# full_Bridge_v2.net
KiCad netlist of a schematic drawn in EAGLE
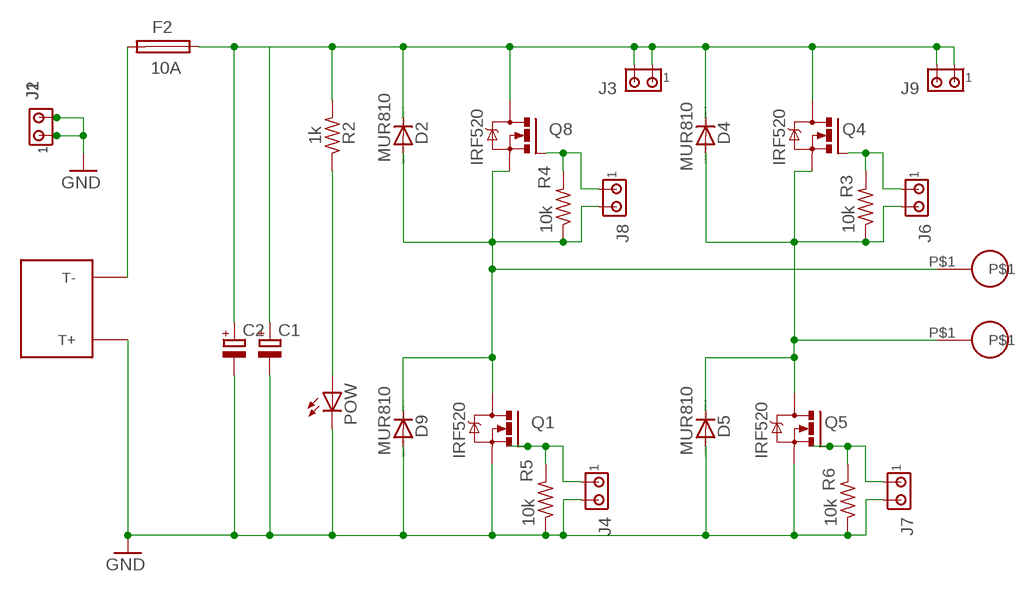
[diagram p0: schematic, sheet 1]

(export (version "E")
  (design (tool "Eeschema 10.0.6"))
  (components
    (comp (ref "AC1")
      (value "TERMINAL")
      (footprint "eagle-import:TERMINAL")
      (libsource (lib "eagle-import") (part "TERMINAL"))
    )
    (comp (ref "AC2")
      (value "TERMINAL")
      (footprint "eagle-import:TERMINAL")
      (libsource (lib "eagle-import") (part "TERMINAL"))
    )
    (comp (ref "C1")
      (value "CPOL-EUTT5D10")
      (footprint "eagle-import:TT5D10")
      (libsource (lib "eagle-import") (part "CPOL-EUTT5D10"))
    )
    (comp (ref "C2")
      (value "CPOL-EUTT5D10")
      (footprint "eagle-import:TT5D10")
      (libsource (lib "eagle-import") (part "CPOL-EUTT5D10"))
    )
    (comp (ref "D2")
      (value "MUR810")
      (footprint "eagle-import:TO220ACS")
      (libsource (lib "eagle-import") (part "MUR810"))
    )
    (comp (ref "D4")
      (value "MUR810")
      (footprint "eagle-import:TO220ACS")
      (libsource (lib "eagle-import") (part "MUR810"))
    )
    (comp (ref "D5")
      (value "MUR810")
      (footprint "eagle-import:TO220ACS")
      (libsource (lib "eagle-import") (part "MUR810"))
    )
    (comp (ref "D9")
      (value "MUR810")
      (footprint "eagle-import:TO220ACS")
      (libsource (lib "eagle-import") (part "MUR810"))
    )
    (comp (ref "F2")
      (value "10A")
      (footprint "eagle-import:SH22,5A")
      (fields (field (name "MPN") "0031.7701.11"))
      (libsource (lib "eagle-import") (part "SH22,5A"))
    )
    (comp (ref "J1")
      (value "MTA02-100")
      (footprint "eagle-import:10X02MTA")
      (libsource (lib "eagle-import") (part "MTA02-100"))
    )
    (comp (ref "J2")
      (value "MTA02-100")
      (footprint "eagle-import:10X02MTA")
      (libsource (lib "eagle-import") (part "MTA02-100"))
    )
    (comp (ref "J3")
      (value "MTA02-100")
      (footprint "eagle-import:10X02MTA")
      (libsource (lib "eagle-import") (part "MTA02-100"))
    )
    (comp (ref "J4")
      (value "MTA02-100")
      (footprint "eagle-import:10X02MTA")
      (libsource (lib "eagle-import") (part "MTA02-100"))
    )
    (comp (ref "J6")
      (value "MTA02-100")
      (footprint "eagle-import:10X02MTA")
      (libsource (lib "eagle-import") (part "MTA02-100"))
    )
    (comp (ref "J7")
      (value "MTA02-100")
      (footprint "eagle-import:10X02MTA")
      (libsource (lib "eagle-import") (part "MTA02-100"))
    )
    (comp (ref "J8")
      (value "MTA02-100")
      (footprint "eagle-import:10X02MTA")
      (libsource (lib "eagle-import") (part "MTA02-100"))
    )
    (comp (ref "J9")
      (value "MTA02-100")
      (footprint "eagle-import:10X02MTA")
      (libsource (lib "eagle-import") (part "MTA02-100"))
    )
    (comp (ref "POW")
      (value "LED3MM")
      (footprint "eagle-import:LED3MM")
      (libsource (lib "eagle-import") (part "LED3MM"))
    )
    (comp (ref "Q1")
      (value "IRF520")
      (footprint "eagle-import:TO220BV")
      (libsource (lib "eagle-import") (part "IRF520"))
    )
    (comp (ref "Q4")
      (value "IRF520")
      (footprint "eagle-import:TO220BV")
      (libsource (lib "eagle-import") (part "IRF520"))
    )
    (comp (ref "Q5")
      (value "IRF520")
      (footprint "eagle-import:TO220BV")
      (libsource (lib "eagle-import") (part "IRF520"))
    )
    (comp (ref "Q8")
      (value "IRF520")
      (footprint "eagle-import:TO220BV")
      (libsource (lib "eagle-import") (part "IRF520"))
    )
    (comp (ref "R2")
      (value "1k")
      (footprint "eagle-import:0207_12")
      (libsource (lib "eagle-import") (part "R-US_0207/12"))
    )
    (comp (ref "R3")
      (value "10k")
      (footprint "eagle-import:0204_7")
      (libsource (lib "eagle-import") (part "R-US_0204/7"))
    )
    (comp (ref "R4")
      (value "10k")
      (footprint "eagle-import:0204_7")
      (libsource (lib "eagle-import") (part "R-US_0204/7"))
    )
    (comp (ref "R5")
      (value "10k")
      (footprint "eagle-import:0204_7")
      (libsource (lib "eagle-import") (part "R-US_0204/7"))
    )
    (comp (ref "R6")
      (value "10k")
      (footprint "eagle-import:0204_7")
      (libsource (lib "eagle-import") (part "R-US_0204/7"))
    )
    (comp (ref "U$5")
      (value "CONNECTOR_BIG")
      (footprint "eagle-import:CONNECTOR_BIG")
      (libsource (lib "eagle-import") (part "CONNECTOR_BIG"))
    )
  )
  (nets
    (net (code "1") (name "GND") (class "Default")
      (node (ref "C1") (pin "-") (pinfunction "-_-") (pintype "passive"))
      (node (ref "C2") (pin "-") (pinfunction "-_-") (pintype "passive"))
      (node (ref "D5") (pin "A") (pinfunction "A_A") (pintype "passive"))
      (node (ref "D9") (pin "A") (pinfunction "A_A") (pintype "passive"))
      (node (ref "J1") (pin "1") (pinfunction "1_1") (pintype "passive"))
      (node (ref "J1") (pin "2") (pinfunction "2_2") (pintype "passive"))
      (node (ref "J2") (pin "1") (pinfunction "1_1") (pintype "passive"))
      (node (ref "J2") (pin "2") (pinfunction "2_2") (pintype "passive"))
      (node (ref "J4") (pin "2") (pinfunction "2_2") (pintype "passive"))
      (node (ref "J7") (pin "2") (pinfunction "2_2") (pintype "passive"))
      (node (ref "POW") (pin "K") (pinfunction "C_K") (pintype "passive"))
      (node (ref "Q1") (pin "S") (pinfunction "S_S") (pintype "passive"))
      (node (ref "Q5") (pin "S") (pinfunction "S_S") (pintype "passive"))
      (node (ref "R5") (pin "1") (pinfunction "1_1") (pintype "passive"))
      (node (ref "R6") (pin "1") (pinfunction "1_1") (pintype "passive"))
      (node (ref "U$5") (pin "P$1") (pinfunction "T+_P$1") (pintype "bidirectional"))
    )
    (net (code "2") (name "Net-(AC1-PadP$1)") (class "Default")
      (node (ref "AC1") (pin "P$1") (pinfunction "P$1_P$1") (pintype "bidirectional"))
      (node (ref "D2") (pin "A") (pinfunction "A_A") (pintype "passive"))
      (node (ref "D9") (pin "C") (pinfunction "C_C") (pintype "passive"))
      (node (ref "J8") (pin "2") (pinfunction "2_2") (pintype "passive"))
      (node (ref "Q1") (pin "D") (pinfunction "D_D") (pintype "passive"))
      (node (ref "Q8") (pin "S") (pinfunction "S_S") (pintype "passive"))
      (node (ref "R4") (pin "1") (pinfunction "1_1") (pintype "passive"))
    )
    (net (code "3") (name "Net-(AC2-PadP$1)") (class "Default")
      (node (ref "AC2") (pin "P$1") (pinfunction "P$1_P$1") (pintype "bidirectional"))
      (node (ref "D4") (pin "A") (pinfunction "A_A") (pintype "passive"))
      (node (ref "D5") (pin "C") (pinfunction "C_C") (pintype "passive"))
      (node (ref "J6") (pin "2") (pinfunction "2_2") (pintype "passive"))
      (node (ref "Q4") (pin "S") (pinfunction "S_S") (pintype "passive"))
      (node (ref "Q5") (pin "D") (pinfunction "D_D") (pintype "passive"))
      (node (ref "R3") (pin "1") (pinfunction "1_1") (pintype "passive"))
    )
    (net (code "4") (name "Net-(C1-Pad+)") (class "Default")
      (node (ref "C1") (pin "+") (pinfunction "+_+") (pintype "passive"))
      (node (ref "C2") (pin "+") (pinfunction "+_+") (pintype "passive"))
      (node (ref "D2") (pin "C") (pinfunction "C_C") (pintype "passive"))
      (node (ref "D4") (pin "C") (pinfunction "C_C") (pintype "passive"))
      (node (ref "F2") (pin "1") (pinfunction "1_1") (pintype "passive"))
      (node (ref "J3") (pin "1") (pinfunction "1_1") (pintype "passive"))
      (node (ref "J3") (pin "2") (pinfunction "2_2") (pintype "passive"))
      (node (ref "J9") (pin "1") (pinfunction "1_1") (pintype "passive"))
      (node (ref "J9") (pin "2") (pinfunction "2_2") (pintype "passive"))
      (node (ref "Q4") (pin "D") (pinfunction "D_D") (pintype "passive"))
      (node (ref "Q8") (pin "D") (pinfunction "D_D") (pintype "passive"))
      (node (ref "R2") (pin "2") (pinfunction "2_2") (pintype "passive"))
    )
    (net (code "5") (name "Net-(J4-Pad1)") (class "Default")
      (node (ref "J4") (pin "1") (pinfunction "1_1") (pintype "passive"))
      (node (ref "Q1") (pin "G") (pinfunction "G_G") (pintype "passive"))
      (node (ref "R5") (pin "2") (pinfunction "2_2") (pintype "passive"))
    )
    (net (code "6") (name "Net-(J6-Pad1)") (class "Default")
      (node (ref "J6") (pin "1") (pinfunction "1_1") (pintype "passive"))
      (node (ref "Q4") (pin "G") (pinfunction "G_G") (pintype "passive"))
      (node (ref "R3") (pin "2") (pinfunction "2_2") (pintype "passive"))
    )
    (net (code "7") (name "Net-(J7-Pad1)") (class "Default")
      (node (ref "J7") (pin "1") (pinfunction "1_1") (pintype "passive"))
      (node (ref "Q5") (pin "G") (pinfunction "G_G") (pintype "passive"))
      (node (ref "R6") (pin "2") (pinfunction "2_2") (pintype "passive"))
    )
    (net (code "8") (name "Net-(J8-Pad1)") (class "Default")
      (node (ref "J8") (pin "1") (pinfunction "1_1") (pintype "passive"))
      (node (ref "Q8") (pin "G") (pinfunction "G_G") (pintype "passive"))
      (node (ref "R4") (pin "2") (pinfunction "2_2") (pintype "passive"))
    )
    (net (code "9") (name "Net-(POW-PadA)") (class "Default")
      (node (ref "POW") (pin "A") (pinfunction "A_A") (pintype "passive"))
      (node (ref "R2") (pin "1") (pinfunction "1_1") (pintype "passive"))
    )
    (net (code "10") (name "Net-(U$5-T-)") (class "Default")
      (node (ref "F2") (pin "2") (pinfunction "2_2") (pintype "passive"))
      (node (ref "U$5") (pin "P$2") (pinfunction "T-_P$2") (pintype "bidirectional"))
    )
  )
)
